# S1.net
KiCad netlist of a schematic drawn in Altium Designer
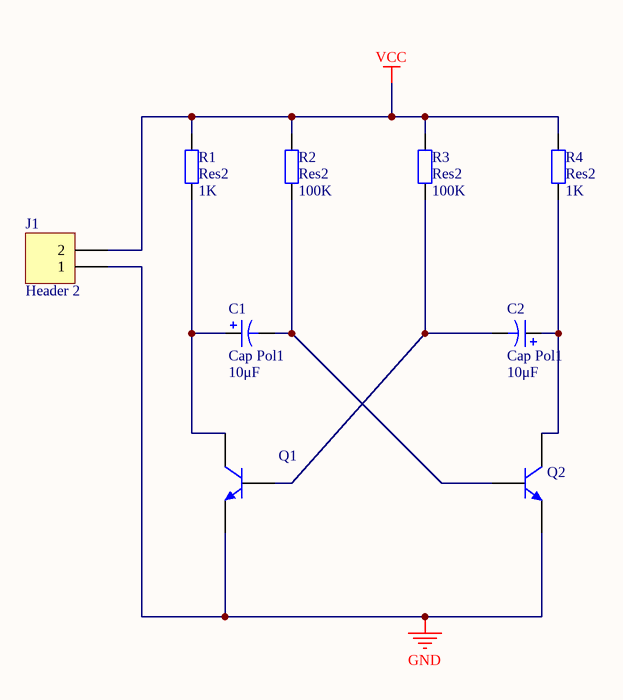
[diagram p0: S1.SchDoc]

(export (version "E")
  (design (tool "Eeschema 10.0.6"))
  (components
    (comp (ref "C1")
      (value "Cap Pol1")
      (footprint "RB7.6-15")
      (description "Polarized Capacitor (Radial)")
      (fields (field (name "ALTIUM_VALUE") "10μF") (field (name "PUBLISHER") "Altium Limited"))
      (libsource (lib "Miscellaneous Devices") (part "Cap Pol1"))
    )
    (comp (ref "C2")
      (value "Cap Pol1")
      (footprint "RB7.6-15")
      (description "Polarized Capacitor (Radial)")
      (fields (field (name "ALTIUM_VALUE") "10μF") (field (name "PUBLISHER") "Altium Limited"))
      (libsource (lib "Miscellaneous Devices") (part "Cap Pol1"))
    )
    (comp (ref "J1")
      (value "Header 2")
      (footprint "HDR1X2")
      (description "Header, 2-Pin")
      (fields (field (name "PUBLISHER") "Altium Limited"))
      (libsource (lib "Miscellaneous Connectors") (part "Header 2"))
    )
    (comp (ref "Q1")
      (value "2N3904")
      (footprint "BCY-W3/E4")
      (description "NPN General Purpose Amplifier")
      (fields (field (name "PUBLISHER") "Altium Limited"))
      (libsource (lib "Miscellaneous Devices") (part "2N3904"))
    )
    (comp (ref "Q2")
      (value "2N3904")
      (footprint "BCY-W3/E4")
      (description "NPN General Purpose Amplifier")
      (fields (field (name "PUBLISHER") "Altium Limited"))
      (libsource (lib "Miscellaneous Devices") (part "2N3904"))
    )
    (comp (ref "R1")
      (value "Res2")
      (footprint "AXIAL-0.4")
      (description "Resistor")
      (fields (field (name "ALTIUM_VALUE") "1K") (field (name "PUBLISHER") "Altium Limited"))
      (libsource (lib "Miscellaneous Devices") (part "Res2"))
    )
    (comp (ref "R2")
      (value "Res2")
      (footprint "AXIAL-0.4")
      (description "Resistor")
      (fields (field (name "ALTIUM_VALUE") "100K") (field (name "PUBLISHER") "Altium Limited"))
      (libsource (lib "Miscellaneous Devices") (part "Res2"))
    )
    (comp (ref "R3")
      (value "Res2")
      (footprint "AXIAL-0.4")
      (description "Resistor")
      (fields (field (name "ALTIUM_VALUE") "100K") (field (name "PUBLISHER") "Altium Limited"))
      (libsource (lib "Miscellaneous Devices") (part "Res2"))
    )
    (comp (ref "R4")
      (value "Res2")
      (footprint "AXIAL-0.4")
      (description "Resistor")
      (fields (field (name "ALTIUM_VALUE") "1K") (field (name "PUBLISHER") "Altium Limited"))
      (libsource (lib "Miscellaneous Devices") (part "Res2"))
    )
  )
  (nets
    (net (code "1") (name "GND") (class "Default")
      (node (ref "J1") (pin "1") (pinfunction "1_1") (pintype "passive"))
      (node (ref "Q1") (pin "1") (pinfunction "E_1") (pintype "passive"))
      (node (ref "Q2") (pin "1") (pinfunction "E_1") (pintype "passive"))
    )
    (net (code "2") (name "Net-(Q1-B)") (class "Default")
      (node (ref "C2") (pin "2") (pinfunction "2_2") (pintype "passive"))
      (node (ref "Q1") (pin "2") (pinfunction "B_2") (pintype "passive"))
      (node (ref "R3") (pin "1") (pinfunction "1_1") (pintype "passive"))
    )
    (net (code "3") (name "Net-(Q1-C)") (class "Default")
      (node (ref "C1") (pin "1") (pinfunction "1_1") (pintype "passive"))
      (node (ref "Q1") (pin "3") (pinfunction "C_3") (pintype "passive"))
      (node (ref "R1") (pin "1") (pinfunction "1_1") (pintype "passive"))
    )
    (net (code "4") (name "Net-(Q2-B)") (class "Default")
      (node (ref "C1") (pin "2") (pinfunction "2_2") (pintype "passive"))
      (node (ref "Q2") (pin "2") (pinfunction "B_2") (pintype "passive"))
      (node (ref "R2") (pin "1") (pinfunction "1_1") (pintype "passive"))
    )
    (net (code "5") (name "Net-(Q2-C)") (class "Default")
      (node (ref "C2") (pin "1") (pinfunction "1_1") (pintype "passive"))
      (node (ref "Q2") (pin "3") (pinfunction "C_3") (pintype "passive"))
      (node (ref "R4") (pin "1") (pinfunction "1_1") (pintype "passive"))
    )
    (net (code "6") (name "VCC") (class "Default")
      (node (ref "J1") (pin "2") (pinfunction "2_2") (pintype "passive"))
      (node (ref "R1") (pin "2") (pinfunction "2_2") (pintype "passive"))
      (node (ref "R2") (pin "2") (pinfunction "2_2") (pintype "passive"))
      (node (ref "R3") (pin "2") (pinfunction "2_2") (pintype "passive"))
      (node (ref "R4") (pin "2") (pinfunction "2_2") (pintype "passive"))
    )
  )
)
